# G11_PowerSelfLock.net
KiCad netlist of a schematic drawn in Altium Designer
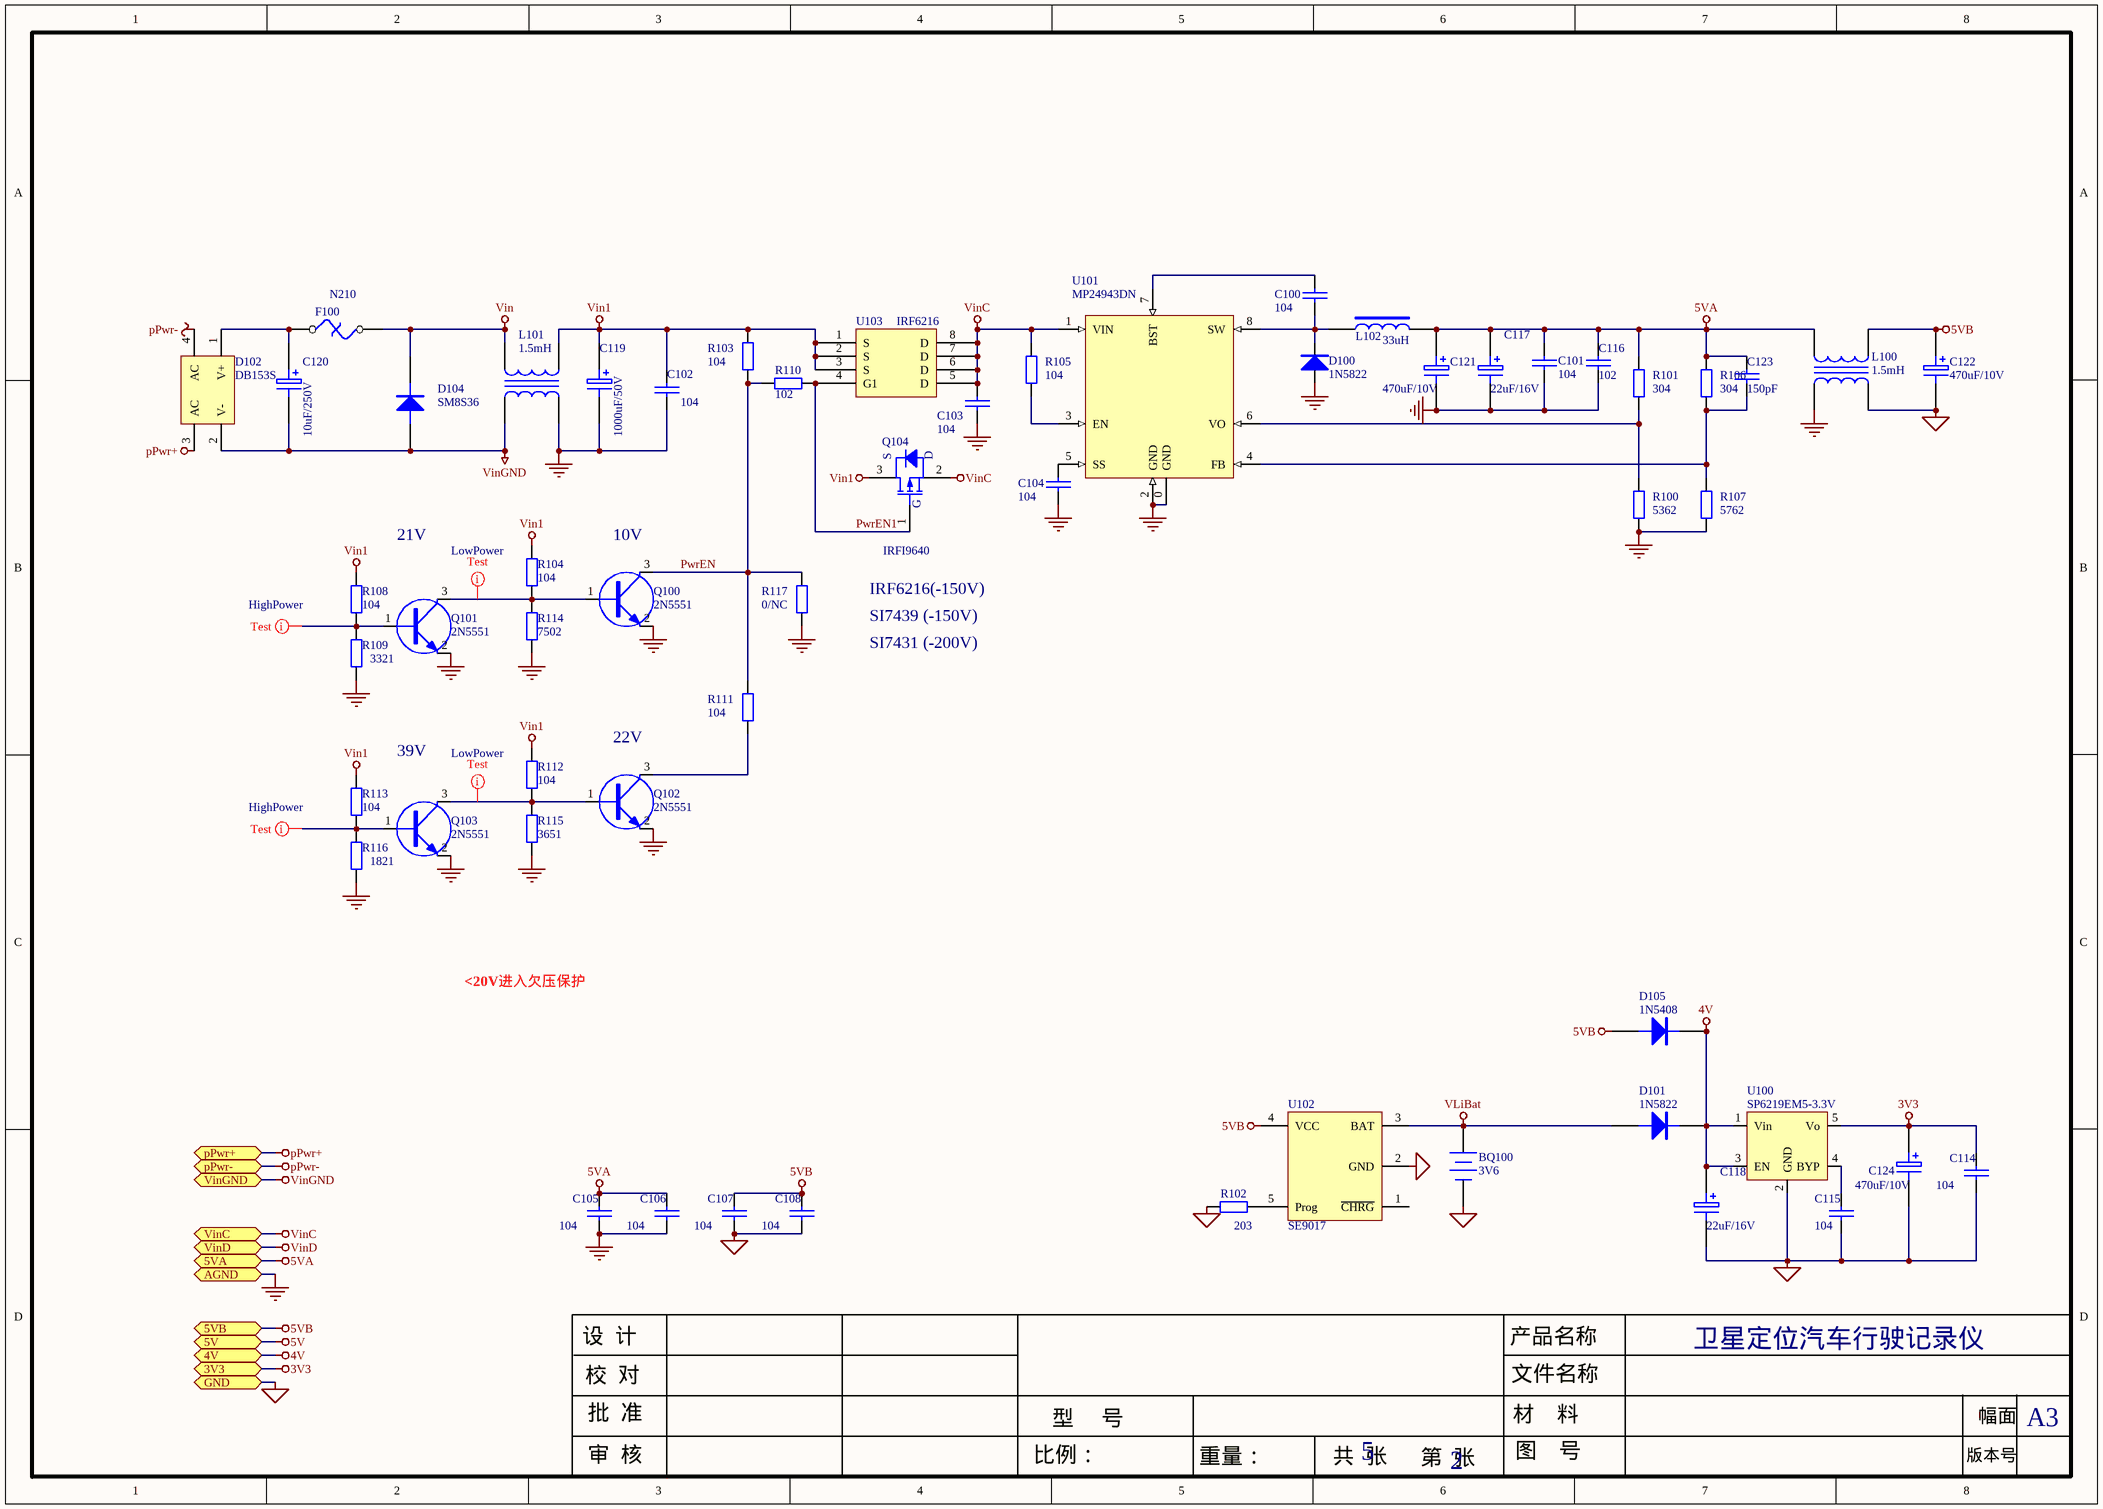
[diagram p0: G11_PowerSelfLock.SCHDOC]

(export (version "E")
  (design (tool "Eeschema 10.0.6"))
  (components
    (comp (ref "BQ100")
      (value "3V6")
      (footprint "BT-2.0")
      (description "2.54锂电池插座")
      (fields (field (name "MANUFACTURER") "Generic Components"))
      (libsource (lib "*") (part "Battery"))
    )
    (comp (ref "C100")
      (value "104")
      (footprint "C0603")
      (description "贴片电容")
      (libsource (lib "*") (part "CAP"))
    )
    (comp (ref "C101")
      (value "104")
      (footprint "C0603")
      (description "贴片电容")
      (libsource (lib "*") (part "CAP"))
    )
    (comp (ref "C102")
      (value "104")
      (footprint "C0603")
      (description "贴片电容")
      (libsource (lib "*") (part "CAP"))
    )
    (comp (ref "C103")
      (value "104")
      (footprint "C0603")
      (description "贴片电容")
      (libsource (lib "*") (part "CAP"))
    )
    (comp (ref "C104")
      (value "104")
      (footprint "C0603")
      (description "贴片电容")
      (libsource (lib "*") (part "CAP"))
    )
    (comp (ref "C105")
      (value "104")
      (footprint "C0603")
      (description "贴片电容")
      (libsource (lib "*") (part "CAP"))
    )
    (comp (ref "C106")
      (value "104")
      (footprint "C0603")
      (description "贴片电容")
      (libsource (lib "*") (part "CAP"))
    )
    (comp (ref "C107")
      (value "104")
      (footprint "C0603")
      (description "贴片电容")
      (libsource (lib "*") (part "CAP"))
    )
    (comp (ref "C108")
      (value "104")
      (footprint "C0603")
      (description "贴片电容")
      (libsource (lib "*") (part "CAP"))
    )
    (comp (ref "C114")
      (value "104")
      (footprint "C0603")
      (description "贴片电容")
      (libsource (lib "*") (part "CAP"))
    )
    (comp (ref "C115")
      (value "104")
      (footprint "C0603")
      (description "贴片电容")
      (libsource (lib "*") (part "CAP"))
    )
    (comp (ref "C116")
      (value "102")
      (footprint "C0603")
      (description "贴片电容")
      (libsource (lib "*") (part "CAP"))
    )
    (comp (ref "C117")
      (value "22uF/16V")
      (footprint "A(3216)")
      (description "贴片钽电容")
      (libsource (lib "GY-M1") (part "ELECTRO1"))
    )
    (comp (ref "C118")
      (value "22uF/16V")
      (footprint "RB-3.5mm")
      (description "贴片钽电容")
      (libsource (lib "GY-M1") (part "ELECTRO1"))
    )
    (comp (ref "C119")
      (value "1000uF/50V")
      (footprint "RB.2/.4")
      (description "直插电解")
      (libsource (lib "*") (part "ELECTRO1"))
    )
    (comp (ref "C120")
      (value "10uF/250V")
      (footprint "RB-3.5mm")
      (description "直插电解")
      (libsource (lib "*") (part "ELECTRO1"))
    )
    (comp (ref "C121")
      (value "470uF/10V")
      (footprint "RB-3.5mm")
      (description "直插电解")
      (libsource (lib "*") (part "ELECTRO1"))
    )
    (comp (ref "C122")
      (value "470uF/10V")
      (footprint "RB-3.5mm")
      (description "直插电解")
      (libsource (lib "*") (part "ELECTRO1"))
    )
    (comp (ref "C123")
      (value "150pF")
      (footprint "C0603")
      (description "贴片电容")
      (libsource (lib "*") (part "CAP"))
    )
    (comp (ref "C124")
      (value "470uF/10V")
      (footprint "RB-3.5mm")
      (description "直插电解")
      (libsource (lib "*") (part "ELECTRO1"))
    )
    (comp (ref "D100")
      (value "1N5822")
      (footprint "D2010")
      (description "贴片二极管")
      (libsource (lib "RecorderMainBoard") (part "DIODE"))
    )
    (comp (ref "D101")
      (value "1N5822")
      (footprint "D2010")
      (description "贴片二极管")
      (libsource (lib "*") (part "DIODE"))
    )
    (comp (ref "D102")
      (value "DB153S")
      (footprint "DB156S")
      (description "整流桥")
      (fields (field (name "PUBLISHER") "Altium Limited"))
      (libsource (lib "GY-G11") (part "Bridge2"))
    )
    (comp (ref "D104")
      (value "SM8S36")
      (footprint "DO-218")
      (description "贴片瞬态抑制二极管")
      (libsource (lib "*") (part "DIODE"))
    )
    (comp (ref "D105")
      (value "1N5408")
      (footprint "D-214")
      (description "贴片二极管")
      (libsource (lib "*") (part "DIODE"))
    )
    (comp (ref "F100")
      (value "N210")
      (footprint "RAD0.2")
      (description "直插自恢保险丝")
      (libsource (lib "*") (part "THERMAL FUSE"))
    )
    (comp (ref "L100")
      (value "1.5mH")
      (footprint "CMH-5p")
      (description "贴片共模电感")
      (fields (field (name "PUBLISHER") "Altium Limited"))
      (libsource (lib "LPC213_General") (part "Trans Adj"))
    )
    (comp (ref "L101")
      (value "1.5mH")
      (footprint "CMH-5p")
      (description "贴片共模电感")
      (fields (field (name "PUBLISHER") "Altium Limited"))
      (libsource (lib "") (part "Trans Adj_1"))
    )
    (comp (ref "L102")
      (value "33uH")
      (footprint "L10uH_H")
      (description "贴片工字电感")
      (libsource (lib "*") (part "INDUCTOR2"))
    )
    (comp (ref "Q100")
      (value "2N5551")
      (footprint "SOT-233")
      (description "贴片三极管")
      (libsource (lib "SimpleGPS") (part "9013"))
    )
    (comp (ref "Q101")
      (value "2N5551")
      (footprint "SOT-233")
      (description "贴片三极管")
      (libsource (lib "SimpleGPS") (part "9013"))
    )
    (comp (ref "Q102")
      (value "2N5551")
      (footprint "SOT-233")
      (description "贴片三极管")
      (libsource (lib "SimpleGPS") (part "9013"))
    )
    (comp (ref "Q103")
      (value "2N5551")
      (footprint "SOT-233")
      (description "贴片三极管")
      (libsource (lib "SimpleGPS") (part "9013"))
    )
    (comp (ref "Q104")
      (value "IRFI9640")
      (footprint "TO-220-3")
      (description "贴片P沟MOS管")
      (libsource (lib "GY-G11") (part "MOSFET-P_1"))
    )
    (comp (ref "R100")
      (value "5362")
      (footprint "R0603")
      (description "贴片电阻")
      (fields
        (field (name "MANUFACTURER") "Generic Components")
        (field (name "PUBLISHER") "Altium Hobart Technology Centre")
      )
      (libsource (lib "GY-VT08M") (part "Res2"))
    )
    (comp (ref "R101")
      (value "304")
      (footprint "R0603")
      (description "贴片电阻")
      (fields
        (field (name "MANUFACTURER") "Generic Components")
        (field (name "PUBLISHER") "Altium Hobart Technology Centre")
      )
      (libsource (lib "GY-VT08M") (part "Res2"))
    )
    (comp (ref "R102")
      (value "203")
      (footprint "R0603")
      (description "贴片电阻")
      (fields
        (field (name "MANUFACTURER") "Generic Components")
        (field (name "PUBLISHER") "Altium Hobart Technology Centre")
      )
      (libsource (lib "LPC213_General") (part "Res2"))
    )
    (comp (ref "R103")
      (value "104")
      (footprint "R0603")
      (description "贴片电阻")
      (fields
        (field (name "MANUFACTURER") "Generic Components")
        (field (name "PUBLISHER") "Altium Hobart Technology Centre")
      )
      (libsource (lib "GY-VT08M") (part "Res2"))
    )
    (comp (ref "R104")
      (value "104")
      (footprint "R0603")
      (description "贴片电阻")
      (fields
        (field (name "MANUFACTURER") "Generic Components")
        (field (name "PUBLISHER") "Altium Hobart Technology Centre")
      )
      (libsource (lib "GY-VT08M") (part "Res2"))
    )
    (comp (ref "R105")
      (value "104")
      (footprint "R0603")
      (description "贴片电阻")
      (fields
        (field (name "MANUFACTURER") "Generic Components")
        (field (name "PUBLISHER") "Altium Hobart Technology Centre")
      )
      (libsource (lib "GY-VT08M") (part "Res2"))
    )
    (comp (ref "R106")
      (value "304")
      (footprint "R0603")
      (description "贴片电阻")
      (fields
        (field (name "MANUFACTURER") "Generic Components")
        (field (name "PUBLISHER") "Altium Hobart Technology Centre")
      )
      (libsource (lib "GY-VT08M") (part "Res2"))
    )
    (comp (ref "R107")
      (value "5762")
      (footprint "R0603")
      (description "贴片电阻")
      (fields
        (field (name "MANUFACTURER") "Generic Components")
        (field (name "PUBLISHER") "Altium Hobart Technology Centre")
      )
      (libsource (lib "GY-VT08M") (part "Res2"))
    )
    (comp (ref "R108")
      (value "104")
      (footprint "R0603")
      (description "贴片电阻")
      (fields
        (field (name "MANUFACTURER") "Generic Components")
        (field (name "PUBLISHER") "Altium Hobart Technology Centre")
      )
      (libsource (lib "GY-VT08M") (part "Res2"))
    )
    (comp (ref "R109")
      (value "3321")
      (footprint "R0603")
      (description "贴片电阻")
      (fields
        (field (name "MANUFACTURER") "Generic Components")
        (field (name "PUBLISHER") "Altium Hobart Technology Centre")
      )
      (libsource (lib "GY-VT08M") (part "Res2"))
    )
    (comp (ref "R110")
      (value "102")
      (footprint "R0603")
      (description "贴片电阻")
      (fields
        (field (name "MANUFACTURER") "Generic Components")
        (field (name "PUBLISHER") "Altium Hobart Technology Centre")
      )
      (libsource (lib "") (part "Res2_1"))
    )
    (comp (ref "R111")
      (value "104")
      (footprint "R0603")
      (description "贴片电阻")
      (fields
        (field (name "MANUFACTURER") "Generic Components")
        (field (name "PUBLISHER") "Altium Hobart Technology Centre")
      )
      (libsource (lib "GY-VT08M") (part "Res2"))
    )
    (comp (ref "R112")
      (value "104")
      (footprint "R0603")
      (description "贴片电阻")
      (fields
        (field (name "MANUFACTURER") "Generic Components")
        (field (name "PUBLISHER") "Altium Hobart Technology Centre")
      )
      (libsource (lib "GY-VT08M") (part "Res2"))
    )
    (comp (ref "R113")
      (value "104")
      (footprint "R0603")
      (description "贴片电阻")
      (fields
        (field (name "MANUFACTURER") "Generic Components")
        (field (name "PUBLISHER") "Altium Hobart Technology Centre")
      )
      (libsource (lib "GY-VT08M") (part "Res2"))
    )
    (comp (ref "R114")
      (value "7502")
      (footprint "R0603")
      (description "贴片电阻")
      (fields
        (field (name "MANUFACTURER") "Generic Components")
        (field (name "PUBLISHER") "Altium Hobart Technology Centre")
      )
      (libsource (lib "GY-VT08M") (part "Res2"))
    )
    (comp (ref "R115")
      (value "3651")
      (footprint "R0603")
      (description "贴片电阻")
      (fields
        (field (name "MANUFACTURER") "Generic Components")
        (field (name "PUBLISHER") "Altium Hobart Technology Centre")
      )
      (libsource (lib "GY-VT08M") (part "Res2"))
    )
    (comp (ref "R116")
      (value "1821")
      (footprint "R0603")
      (description "贴片电阻")
      (fields
        (field (name "MANUFACTURER") "Generic Components")
        (field (name "PUBLISHER") "Altium Hobart Technology Centre")
      )
      (libsource (lib "GY-VT08M") (part "Res2"))
    )
    (comp (ref "R117")
      (value "0/NC")
      (footprint "R0603")
      (description "贴片电阻")
      (fields
        (field (name "MANUFACTURER") "Generic Components")
        (field (name "PUBLISHER") "Altium Hobart Technology Centre")
      )
      (libsource (lib "GY-VT08M") (part "Res2"))
    )
    (comp (ref "U100")
      (value "SP6219EM5-3.3V")
      (footprint "SOT-235")
      (description "贴片电源IC")
      (libsource (lib "*") (part "SPX5205"))
    )
    (comp (ref "U101")
      (value "MP24943DN")
      (footprint "SOP8-Hot")
      (description "IC 同步降压IC")
      (libsource (lib "GY-G11") (part "MP24943DN"))
    )
    (comp (ref "U102")
      (value "SE9017")
      (footprint "SOT-235")
      (description "贴片充电IC")
      (libsource (lib "GPS_Recorder_LPC210x") (part "SE9016"))
    )
    (comp (ref "U103")
      (value "IRF6216")
      (footprint "SOP8-Power")
      (description "贴片PMOS管")
      (libsource (lib "GY-G10B-V2.0") (part "IRF7853"))
    )
  )
  (nets
    (net (code "1") (name "/PwrEN") (class "Default")
      (node (ref "Q100") (pin "3") (pinfunction "C_3") (pintype "passive"))
      (node (ref "R103") (pin "1") (pinfunction "1_1") (pintype "passive"))
      (node (ref "R110") (pin "2") (pinfunction "2_2") (pintype "passive"))
      (node (ref "R111") (pin "2") (pinfunction "2_2") (pintype "passive"))
      (node (ref "R117") (pin "2") (pinfunction "2_2") (pintype "passive"))
    )
    (net (code "2") (name "/PwrEN1") (class "Default")
      (node (ref "Q104") (pin "1") (pinfunction "G_1") (pintype "passive"))
      (node (ref "R110") (pin "1") (pinfunction "1_1") (pintype "passive"))
      (node (ref "U103") (pin "4") (pinfunction "G1_4") (pintype "passive"))
    )
    (net (code "3") (name "3V3") (class "Default")
      (node (ref "C114") (pin "1") (pinfunction "1_1") (pintype "passive"))
      (node (ref "C124") (pin "1") (pinfunction "1_1") (pintype "passive"))
      (node (ref "U100") (pin "5") (pinfunction "Vo_5") (pintype "passive"))
    )
    (net (code "4") (name "4V") (class "Default")
      (node (ref "C118") (pin "1") (pinfunction "1_1") (pintype "passive"))
      (node (ref "D101") (pin "2") (pinfunction "2_2") (pintype "passive"))
      (node (ref "D105") (pin "2") (pinfunction "2_2") (pintype "passive"))
      (node (ref "U100") (pin "1") (pinfunction "Vin_1") (pintype "passive"))
      (node (ref "U100") (pin "3") (pinfunction "EN_3") (pintype "passive"))
    )
    (net (code "6") (name "5VA") (class "Default")
      (node (ref "C101") (pin "2") (pinfunction "2_2") (pintype "passive"))
      (node (ref "C105") (pin "1") (pinfunction "1_1") (pintype "passive"))
      (node (ref "C106") (pin "1") (pinfunction "1_1") (pintype "passive"))
      (node (ref "C116") (pin "2") (pinfunction "2_2") (pintype "passive"))
      (node (ref "C117") (pin "1") (pinfunction "1_1") (pintype "passive"))
      (node (ref "C121") (pin "1") (pinfunction "1_1") (pintype "passive"))
      (node (ref "C123") (pin "2") (pinfunction "2_2") (pintype "passive"))
      (node (ref "L100") (pin "1") (pinfunction "1_1") (pintype "passive"))
      (node (ref "L102") (pin "2") (pinfunction "2_2") (pintype "passive"))
      (node (ref "R101") (pin "2") (pinfunction "2_2") (pintype "passive"))
      (node (ref "R106") (pin "2") (pinfunction "2_2") (pintype "passive"))
    )
    (net (code "7") (name "5VB") (class "Default")
      (node (ref "C107") (pin "1") (pinfunction "1_1") (pintype "passive"))
      (node (ref "C108") (pin "1") (pinfunction "1_1") (pintype "passive"))
      (node (ref "C122") (pin "1") (pinfunction "1_1") (pintype "passive"))
      (node (ref "D105") (pin "1") (pinfunction "1_1") (pintype "passive"))
      (node (ref "L100") (pin "3") (pinfunction "3_3") (pintype "passive"))
      (node (ref "U102") (pin "4") (pinfunction "VCC_4") (pintype "passive"))
    )
    (net (code "8") (name "AGND") (class "Default")
      (node (ref "C101") (pin "1") (pinfunction "1_1") (pintype "passive"))
      (node (ref "C102") (pin "2") (pinfunction "2_2") (pintype "passive"))
      (node (ref "C103") (pin "2") (pinfunction "2_2") (pintype "passive"))
      (node (ref "C104") (pin "2") (pinfunction "2_2") (pintype "passive"))
      (node (ref "C105") (pin "2") (pinfunction "2_2") (pintype "passive"))
      (node (ref "C106") (pin "2") (pinfunction "2_2") (pintype "passive"))
      (node (ref "C116") (pin "1") (pinfunction "1_1") (pintype "passive"))
      (node (ref "C117") (pin "2") (pinfunction "2_2") (pintype "passive"))
      (node (ref "C119") (pin "2") (pinfunction "2_2") (pintype "passive"))
      (node (ref "C121") (pin "2") (pinfunction "2_2") (pintype "passive"))
      (node (ref "D100") (pin "1") (pinfunction "1_1") (pintype "passive"))
      (node (ref "L100") (pin "2") (pinfunction "2_2") (pintype "passive"))
      (node (ref "L101") (pin "2") (pinfunction "2_2") (pintype "passive"))
      (node (ref "Q100") (pin "2") (pinfunction "E_2") (pintype "passive"))
      (node (ref "Q101") (pin "2") (pinfunction "E_2") (pintype "passive"))
      (node (ref "Q102") (pin "2") (pinfunction "E_2") (pintype "passive"))
      (node (ref "Q103") (pin "2") (pinfunction "E_2") (pintype "passive"))
      (node (ref "R100") (pin "1") (pinfunction "1_1") (pintype "passive"))
      (node (ref "R107") (pin "1") (pinfunction "1_1") (pintype "passive"))
      (node (ref "R109") (pin "1") (pinfunction "1_1") (pintype "passive"))
      (node (ref "R114") (pin "1") (pinfunction "1_1") (pintype "passive"))
      (node (ref "R115") (pin "1") (pinfunction "1_1") (pintype "passive"))
      (node (ref "R116") (pin "1") (pinfunction "1_1") (pintype "passive"))
      (node (ref "R117") (pin "1") (pinfunction "1_1") (pintype "passive"))
      (node (ref "U101") (pin "0") (pinfunction "GND_0") (pintype "power_in"))
      (node (ref "U101") (pin "2") (pinfunction "GND_2") (pintype "input"))
    )
    (net (code "9") (name "GND") (class "Default")
      (node (ref "BQ100") (pin "2") (pinfunction "-_2") (pintype "passive"))
      (node (ref "C107") (pin "2") (pinfunction "2_2") (pintype "passive"))
      (node (ref "C108") (pin "2") (pinfunction "2_2") (pintype "passive"))
      (node (ref "C114") (pin "2") (pinfunction "2_2") (pintype "passive"))
      (node (ref "C115") (pin "1") (pinfunction "1_1") (pintype "passive"))
      (node (ref "C118") (pin "2") (pinfunction "2_2") (pintype "passive"))
      (node (ref "C122") (pin "2") (pinfunction "2_2") (pintype "passive"))
      (node (ref "C124") (pin "2") (pinfunction "2_2") (pintype "passive"))
      (node (ref "L100") (pin "4") (pinfunction "4_4") (pintype "passive"))
      (node (ref "R102") (pin "2") (pinfunction "2_2") (pintype "passive"))
      (node (ref "U100") (pin "2") (pinfunction "GND_2") (pintype "passive"))
      (node (ref "U102") (pin "2") (pinfunction "GND_2") (pintype "passive"))
    )
    (net (code "10") (name "Net-(D102-V+)") (class "Default")
      (node (ref "C120") (pin "1") (pinfunction "1_1") (pintype "passive"))
      (node (ref "D102") (pin "1") (pinfunction "V+_1") (pintype "passive"))
      (node (ref "F100") (pin "1") (pinfunction "1_1") (pintype "passive"))
    )
    (net (code "11") (name "Net-(Q100-B)") (class "Default")
      (node (ref "Q100") (pin "1") (pinfunction "B_1") (pintype "passive"))
      (node (ref "Q101") (pin "3") (pinfunction "C_3") (pintype "passive"))
      (node (ref "R104") (pin "1") (pinfunction "1_1") (pintype "passive"))
      (node (ref "R114") (pin "2") (pinfunction "2_2") (pintype "passive"))
    )
    (net (code "12") (name "Net-(Q101-B)") (class "Default")
      (node (ref "Q101") (pin "1") (pinfunction "B_1") (pintype "passive"))
      (node (ref "R108") (pin "1") (pinfunction "1_1") (pintype "passive"))
      (node (ref "R109") (pin "2") (pinfunction "2_2") (pintype "passive"))
    )
    (net (code "13") (name "Net-(Q102-B)") (class "Default")
      (node (ref "Q102") (pin "1") (pinfunction "B_1") (pintype "passive"))
      (node (ref "Q103") (pin "3") (pinfunction "C_3") (pintype "passive"))
      (node (ref "R112") (pin "1") (pinfunction "1_1") (pintype "passive"))
      (node (ref "R115") (pin "2") (pinfunction "2_2") (pintype "passive"))
    )
    (net (code "14") (name "Net-(Q102-C)") (class "Default")
      (node (ref "Q102") (pin "3") (pinfunction "C_3") (pintype "passive"))
      (node (ref "R111") (pin "1") (pinfunction "1_1") (pintype "passive"))
    )
    (net (code "15") (name "Net-(Q103-B)") (class "Default")
      (node (ref "Q103") (pin "1") (pinfunction "B_1") (pintype "passive"))
      (node (ref "R113") (pin "1") (pinfunction "1_1") (pintype "passive"))
      (node (ref "R116") (pin "2") (pinfunction "2_2") (pintype "passive"))
    )
    (net (code "16") (name "Net-(U100-BYP)") (class "Default")
      (node (ref "C115") (pin "2") (pinfunction "2_2") (pintype "passive"))
      (node (ref "U100") (pin "4") (pinfunction "BYP_4") (pintype "passive"))
    )
    (net (code "17") (name "Net-(U101-BST)") (class "Default")
      (node (ref "C100") (pin "1") (pinfunction "1_1") (pintype "passive"))
      (node (ref "U101") (pin "7") (pinfunction "BST_7") (pintype "input"))
    )
    (net (code "18") (name "Net-(U101-EN)") (class "Default")
      (node (ref "R105") (pin "1") (pinfunction "1_1") (pintype "passive"))
      (node (ref "U101") (pin "3") (pinfunction "EN_3") (pintype "input"))
    )
    (net (code "19") (name "Net-(U101-FB)") (class "Default")
      (node (ref "C123") (pin "1") (pinfunction "1_1") (pintype "passive"))
      (node (ref "R106") (pin "1") (pinfunction "1_1") (pintype "passive"))
      (node (ref "R107") (pin "2") (pinfunction "2_2") (pintype "passive"))
      (node (ref "U101") (pin "4") (pinfunction "FB_4") (pintype "input"))
    )
    (net (code "20") (name "Net-(U101-SS)") (class "Default")
      (node (ref "C104") (pin "1") (pinfunction "1_1") (pintype "passive"))
      (node (ref "U101") (pin "5") (pinfunction "SS_5") (pintype "input"))
    )
    (net (code "21") (name "Net-(U101-SW)") (class "Default")
      (node (ref "C100") (pin "2") (pinfunction "2_2") (pintype "passive"))
      (node (ref "D100") (pin "2") (pinfunction "2_2") (pintype "passive"))
      (node (ref "L102") (pin "1") (pinfunction "1_1") (pintype "passive"))
      (node (ref "U101") (pin "8") (pinfunction "SW_8") (pintype "input"))
    )
    (net (code "22") (name "Net-(U101-VO)") (class "Default")
      (node (ref "R100") (pin "2") (pinfunction "2_2") (pintype "passive"))
      (node (ref "R101") (pin "1") (pinfunction "1_1") (pintype "passive"))
      (node (ref "U101") (pin "6") (pinfunction "VO_6") (pintype "input"))
    )
    (net (code "23") (name "Net-(U102-BYP)") (class "Default")
      (node (ref "U102") (pin "4") (pinfunction "BYP_4") (pintype "passive"))
    )
    (net (code "24") (name "Net-(U102-EN)") (class "Default")
      (node (ref "U102") (pin "3") (pinfunction "EN_3") (pintype "passive"))
    )
    (net (code "25") (name "Net-(U102-GND)") (class "Default")
      (node (ref "U102") (pin "2") (pinfunction "GND_2") (pintype "passive"))
    )
    (net (code "26") (name "Net-(U102-Prog)") (class "Default")
      (node (ref "R102") (pin "1") (pinfunction "1_1") (pintype "passive"))
      (node (ref "U102") (pin "5") (pinfunction "Prog_5") (pintype "passive"))
    )
    (net (code "27") (name "Net-(U102-Vin)") (class "Default")
      (node (ref "U102") (pin "1") (pinfunction "Vin_1") (pintype "passive"))
    )
    (net (code "28") (name "Net-(U102-Vo)") (class "Default")
      (node (ref "U102") (pin "5") (pinfunction "Vo_5") (pintype "passive"))
    )
    (net (code "29") (name "VLiBat") (class "Default")
      (node (ref "BQ100") (pin "1") (pinfunction "+_1") (pintype "passive"))
      (node (ref "D101") (pin "1") (pinfunction "1_1") (pintype "passive"))
      (node (ref "U102") (pin "3") (pinfunction "BAT_3") (pintype "passive"))
    )
    (net (code "30") (name "Vin") (class "Default")
      (node (ref "D104") (pin "2") (pinfunction "2_2") (pintype "passive"))
      (node (ref "F100") (pin "2") (pinfunction "2_2") (pintype "passive"))
      (node (ref "L101") (pin "3") (pinfunction "3_3") (pintype "passive"))
    )
    (net (code "31") (name "Vin1") (class "Default")
      (node (ref "C102") (pin "1") (pinfunction "1_1") (pintype "passive"))
      (node (ref "C119") (pin "1") (pinfunction "1_1") (pintype "passive"))
      (node (ref "L101") (pin "1") (pinfunction "1_1") (pintype "passive"))
      (node (ref "Q104") (pin "3") (pinfunction "S_3") (pintype "passive"))
      (node (ref "R103") (pin "2") (pinfunction "2_2") (pintype "passive"))
      (node (ref "R104") (pin "2") (pinfunction "2_2") (pintype "passive"))
      (node (ref "R108") (pin "2") (pinfunction "2_2") (pintype "passive"))
      (node (ref "R112") (pin "2") (pinfunction "2_2") (pintype "passive"))
      (node (ref "R113") (pin "2") (pinfunction "2_2") (pintype "passive"))
      (node (ref "U103") (pin "1") (pinfunction "S_1") (pintype "passive"))
      (node (ref "U103") (pin "2") (pinfunction "S_2") (pintype "passive"))
      (node (ref "U103") (pin "3") (pinfunction "S_3") (pintype "passive"))
    )
    (net (code "32") (name "VinC") (class "Default")
      (node (ref "C103") (pin "1") (pinfunction "1_1") (pintype "passive"))
      (node (ref "Q104") (pin "2") (pinfunction "D_2") (pintype "passive"))
      (node (ref "R105") (pin "2") (pinfunction "2_2") (pintype "passive"))
      (node (ref "U101") (pin "1") (pinfunction "VIN_1") (pintype "input"))
      (node (ref "U103") (pin "5") (pinfunction "D_5") (pintype "passive"))
      (node (ref "U103") (pin "6") (pinfunction "D_6") (pintype "passive"))
      (node (ref "U103") (pin "7") (pinfunction "D_7") (pintype "passive"))
      (node (ref "U103") (pin "8") (pinfunction "D_8") (pintype "passive"))
    )
    (net (code "34") (name "VinGND") (class "Default")
      (node (ref "C120") (pin "2") (pinfunction "2_2") (pintype "passive"))
      (node (ref "D102") (pin "2") (pinfunction "V-_2") (pintype "passive"))
      (node (ref "D104") (pin "1") (pinfunction "1_1") (pintype "passive"))
      (node (ref "L101") (pin "4") (pinfunction "4_4") (pintype "passive"))
    )
    (net (code "35") (name "pPwr+") (class "Default")
      (node (ref "D102") (pin "3") (pinfunction "AC_3") (pintype "passive"))
    )
    (net (code "36") (name "pPwr-") (class "Default")
      (node (ref "D102") (pin "4") (pinfunction "AC_4") (pintype "passive"))
    )
    (net (code "37") (name "unconnected-(U102-~{CHRG}-Pad1)") (class "Default")
      (node (ref "U102") (pin "1") (pinfunction "~{CHRG}_1") (pintype "passive"))
    )
  )
)
